# 00A-94.net
KiCad netlist of a schematic drawn in EAGLE
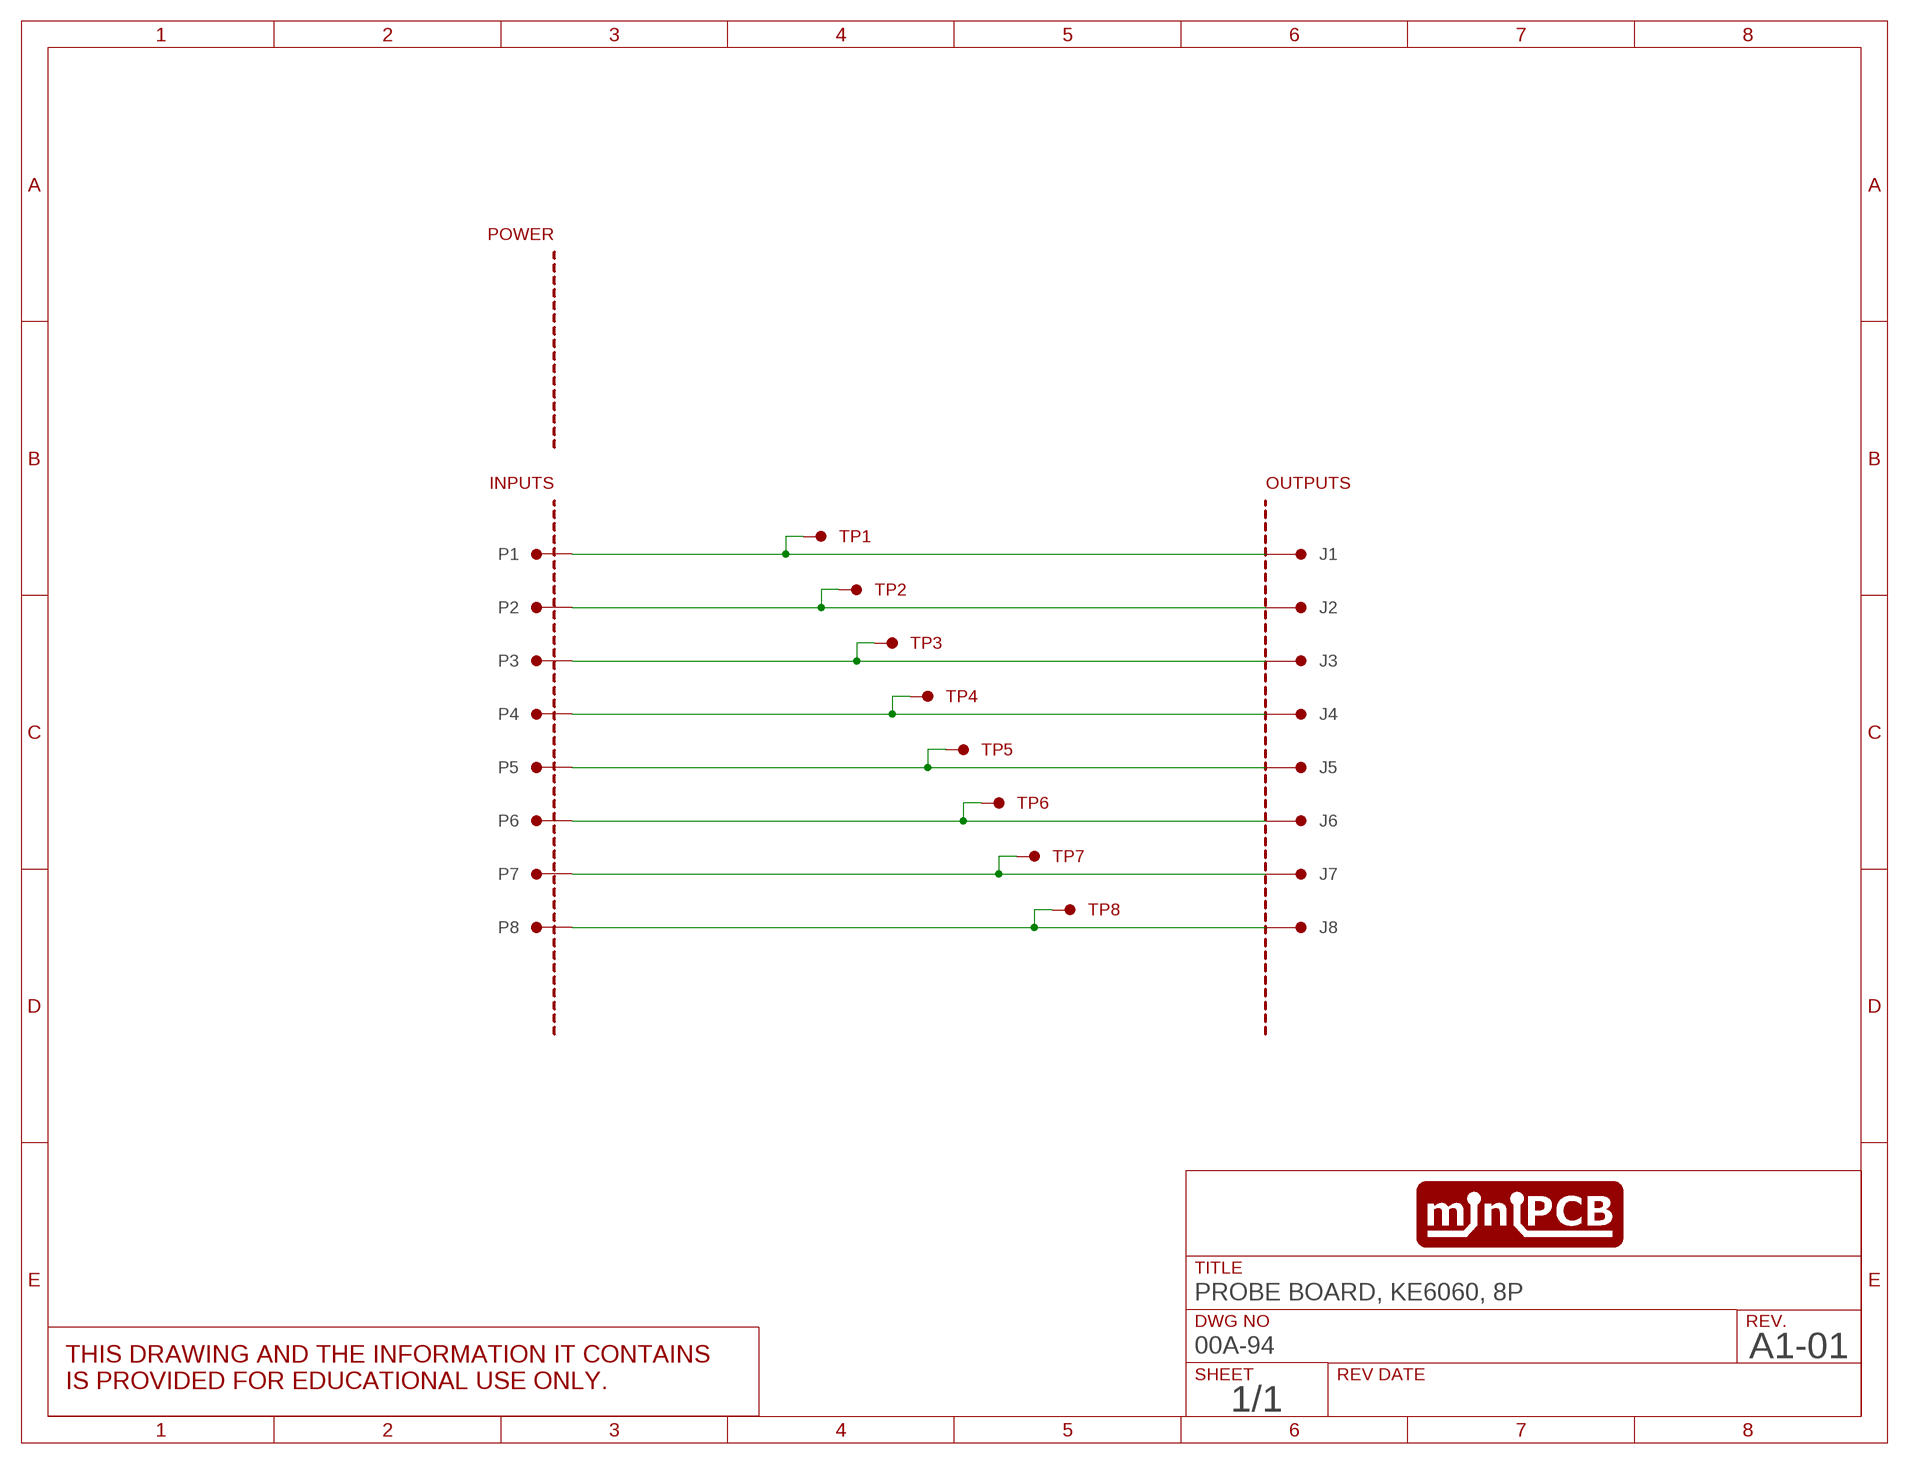
[diagram p0: schematic, sheet 1]

(export (version "E")
  (design (tool "Eeschema 10.0.6"))
  (components
    (comp (ref "J1")
      (value "PINS_1KE6060")
      (footprint "eagle-import:PINS_1_KE6060")
      (libsource (lib "eagle-import") (part "PINS_1KE6060"))
    )
    (comp (ref "J2")
      (value "PINS_1KE6060")
      (footprint "eagle-import:PINS_1_KE6060")
      (libsource (lib "eagle-import") (part "PINS_1KE6060"))
    )
    (comp (ref "J3")
      (value "PINS_1KE6060")
      (footprint "eagle-import:PINS_1_KE6060")
      (libsource (lib "eagle-import") (part "PINS_1KE6060"))
    )
    (comp (ref "J4")
      (value "PINS_1KE6060")
      (footprint "eagle-import:PINS_1_KE6060")
      (libsource (lib "eagle-import") (part "PINS_1KE6060"))
    )
    (comp (ref "J5")
      (value "PINS_1KE6060")
      (footprint "eagle-import:PINS_1_KE6060")
      (libsource (lib "eagle-import") (part "PINS_1KE6060"))
    )
    (comp (ref "J6")
      (value "PINS_1KE6060")
      (footprint "eagle-import:PINS_1_KE6060")
      (libsource (lib "eagle-import") (part "PINS_1KE6060"))
    )
    (comp (ref "J7")
      (value "PINS_1KE6060")
      (footprint "eagle-import:PINS_1_KE6060")
      (libsource (lib "eagle-import") (part "PINS_1KE6060"))
    )
    (comp (ref "J8")
      (value "PINS_1KE6060")
      (footprint "eagle-import:PINS_1_KE6060")
      (libsource (lib "eagle-import") (part "PINS_1KE6060"))
    )
    (comp (ref "P1")
      (value "PINS_124AWG-NOTEXT")
      (footprint "eagle-import:PINS_1_1MM-NOTEXT")
      (libsource (lib "eagle-import") (part "PINS_124AWG-NOTEXT"))
    )
    (comp (ref "P2")
      (value "PINS_124AWG-NOTEXT")
      (footprint "eagle-import:PINS_1_1MM-NOTEXT")
      (libsource (lib "eagle-import") (part "PINS_124AWG-NOTEXT"))
    )
    (comp (ref "P3")
      (value "PINS_124AWG-NOTEXT")
      (footprint "eagle-import:PINS_1_1MM-NOTEXT")
      (libsource (lib "eagle-import") (part "PINS_124AWG-NOTEXT"))
    )
    (comp (ref "P4")
      (value "PINS_124AWG-NOTEXT")
      (footprint "eagle-import:PINS_1_1MM-NOTEXT")
      (libsource (lib "eagle-import") (part "PINS_124AWG-NOTEXT"))
    )
    (comp (ref "P5")
      (value "PINS_124AWG-NOTEXT")
      (footprint "eagle-import:PINS_1_1MM-NOTEXT")
      (libsource (lib "eagle-import") (part "PINS_124AWG-NOTEXT"))
    )
    (comp (ref "P6")
      (value "PINS_124AWG-NOTEXT")
      (footprint "eagle-import:PINS_1_1MM-NOTEXT")
      (libsource (lib "eagle-import") (part "PINS_124AWG-NOTEXT"))
    )
    (comp (ref "P7")
      (value "PINS_124AWG-NOTEXT")
      (footprint "eagle-import:PINS_1_1MM-NOTEXT")
      (libsource (lib "eagle-import") (part "PINS_124AWG-NOTEXT"))
    )
    (comp (ref "P8")
      (value "PINS_124AWG-NOTEXT")
      (footprint "eagle-import:PINS_1_1MM-NOTEXT")
      (libsource (lib "eagle-import") (part "PINS_124AWG-NOTEXT"))
    )
    (comp (ref "PCB1")
      (value "MINIPCB_0P00A-20X100")
      (footprint "eagle-import:MINIPCB_00A_20X100")
      (fields (field (name "PART_NUMBER") "00A-94-A1-01"))
      (libsource (lib "eagle-import") (part "MINIPCB_0P00A-20X100"))
    )
    (comp (ref "TP1")
      (value "TESTPOINTKE5000-SMTEXT")
      (footprint "eagle-import:PINS_1_TESTPOINT_KE5000_NOTEXT")
      (libsource (lib "eagle-import") (part "TESTPOINTKE5000-SMTEXT"))
    )
    (comp (ref "TP2")
      (value "TESTPOINTKE5000-SMTEXT")
      (footprint "eagle-import:PINS_1_TESTPOINT_KE5000_NOTEXT")
      (libsource (lib "eagle-import") (part "TESTPOINTKE5000-SMTEXT"))
    )
    (comp (ref "TP3")
      (value "TESTPOINTKE5000-SMTEXT")
      (footprint "eagle-import:PINS_1_TESTPOINT_KE5000_NOTEXT")
      (libsource (lib "eagle-import") (part "TESTPOINTKE5000-SMTEXT"))
    )
    (comp (ref "TP4")
      (value "TESTPOINTKE5000-SMTEXT")
      (footprint "eagle-import:PINS_1_TESTPOINT_KE5000_NOTEXT")
      (libsource (lib "eagle-import") (part "TESTPOINTKE5000-SMTEXT"))
    )
    (comp (ref "TP5")
      (value "TESTPOINTKE5000-SMTEXT")
      (footprint "eagle-import:PINS_1_TESTPOINT_KE5000_NOTEXT")
      (libsource (lib "eagle-import") (part "TESTPOINTKE5000-SMTEXT"))
    )
    (comp (ref "TP6")
      (value "TESTPOINTKE5000-SMTEXT")
      (footprint "eagle-import:PINS_1_TESTPOINT_KE5000_NOTEXT")
      (libsource (lib "eagle-import") (part "TESTPOINTKE5000-SMTEXT"))
    )
    (comp (ref "TP7")
      (value "TESTPOINTKE5000-SMTEXT")
      (footprint "eagle-import:PINS_1_TESTPOINT_KE5000_NOTEXT")
      (libsource (lib "eagle-import") (part "TESTPOINTKE5000-SMTEXT"))
    )
    (comp (ref "TP8")
      (value "TESTPOINTKE5000-SMTEXT")
      (footprint "eagle-import:PINS_1_TESTPOINT_KE5000_NOTEXT")
      (libsource (lib "eagle-import") (part "TESTPOINTKE5000-SMTEXT"))
    )
  )
  (nets
    (net (code "1") (name "Net-(J1-1-Pad2)") (class "Default")
      (node (ref "J1") (pin "1") (pinfunction "1_1") (pintype "bidirectional"))
      (node (ref "J1") (pin "2") (pinfunction "1_2") (pintype "bidirectional"))
      (node (ref "P1") (pin "1") (pinfunction "1_1") (pintype "bidirectional"))
      (node (ref "P1") (pin "2") (pinfunction "1_2") (pintype "bidirectional"))
      (node (ref "TP1") (pin "1") (pinfunction "1_1") (pintype "bidirectional"))
    )
    (net (code "2") (name "Net-(J2-1-Pad2)") (class "Default")
      (node (ref "J2") (pin "1") (pinfunction "1_1") (pintype "bidirectional"))
      (node (ref "J2") (pin "2") (pinfunction "1_2") (pintype "bidirectional"))
      (node (ref "P2") (pin "1") (pinfunction "1_1") (pintype "bidirectional"))
      (node (ref "P2") (pin "2") (pinfunction "1_2") (pintype "bidirectional"))
      (node (ref "TP2") (pin "1") (pinfunction "1_1") (pintype "bidirectional"))
    )
    (net (code "3") (name "Net-(J3-1-Pad2)") (class "Default")
      (node (ref "J3") (pin "1") (pinfunction "1_1") (pintype "bidirectional"))
      (node (ref "J3") (pin "2") (pinfunction "1_2") (pintype "bidirectional"))
      (node (ref "P3") (pin "1") (pinfunction "1_1") (pintype "bidirectional"))
      (node (ref "P3") (pin "2") (pinfunction "1_2") (pintype "bidirectional"))
      (node (ref "TP3") (pin "1") (pinfunction "1_1") (pintype "bidirectional"))
    )
    (net (code "4") (name "Net-(J4-1-Pad2)") (class "Default")
      (node (ref "J4") (pin "1") (pinfunction "1_1") (pintype "bidirectional"))
      (node (ref "J4") (pin "2") (pinfunction "1_2") (pintype "bidirectional"))
      (node (ref "P4") (pin "1") (pinfunction "1_1") (pintype "bidirectional"))
      (node (ref "P4") (pin "2") (pinfunction "1_2") (pintype "bidirectional"))
      (node (ref "TP4") (pin "1") (pinfunction "1_1") (pintype "bidirectional"))
    )
    (net (code "5") (name "Net-(J5-1-Pad2)") (class "Default")
      (node (ref "J5") (pin "1") (pinfunction "1_1") (pintype "bidirectional"))
      (node (ref "J5") (pin "2") (pinfunction "1_2") (pintype "bidirectional"))
      (node (ref "P5") (pin "1") (pinfunction "1_1") (pintype "bidirectional"))
      (node (ref "P5") (pin "2") (pinfunction "1_2") (pintype "bidirectional"))
      (node (ref "TP5") (pin "1") (pinfunction "1_1") (pintype "bidirectional"))
    )
    (net (code "6") (name "Net-(J6-1-Pad2)") (class "Default")
      (node (ref "J6") (pin "1") (pinfunction "1_1") (pintype "bidirectional"))
      (node (ref "J6") (pin "2") (pinfunction "1_2") (pintype "bidirectional"))
      (node (ref "P6") (pin "1") (pinfunction "1_1") (pintype "bidirectional"))
      (node (ref "P6") (pin "2") (pinfunction "1_2") (pintype "bidirectional"))
      (node (ref "TP6") (pin "1") (pinfunction "1_1") (pintype "bidirectional"))
    )
    (net (code "7") (name "Net-(J7-1-Pad2)") (class "Default")
      (node (ref "J7") (pin "1") (pinfunction "1_1") (pintype "bidirectional"))
      (node (ref "J7") (pin "2") (pinfunction "1_2") (pintype "bidirectional"))
      (node (ref "P7") (pin "1") (pinfunction "1_1") (pintype "bidirectional"))
      (node (ref "P7") (pin "2") (pinfunction "1_2") (pintype "bidirectional"))
      (node (ref "TP7") (pin "1") (pinfunction "1_1") (pintype "bidirectional"))
    )
    (net (code "8") (name "Net-(J8-1-Pad2)") (class "Default")
      (node (ref "J8") (pin "1") (pinfunction "1_1") (pintype "bidirectional"))
      (node (ref "J8") (pin "2") (pinfunction "1_2") (pintype "bidirectional"))
      (node (ref "P8") (pin "1") (pinfunction "1_1") (pintype "bidirectional"))
      (node (ref "P8") (pin "2") (pinfunction "1_2") (pintype "bidirectional"))
      (node (ref "TP8") (pin "1") (pinfunction "1_1") (pintype "bidirectional"))
    )
  )
)
